# 086-005.net
KiCad netlist of a schematic drawn in EAGLE
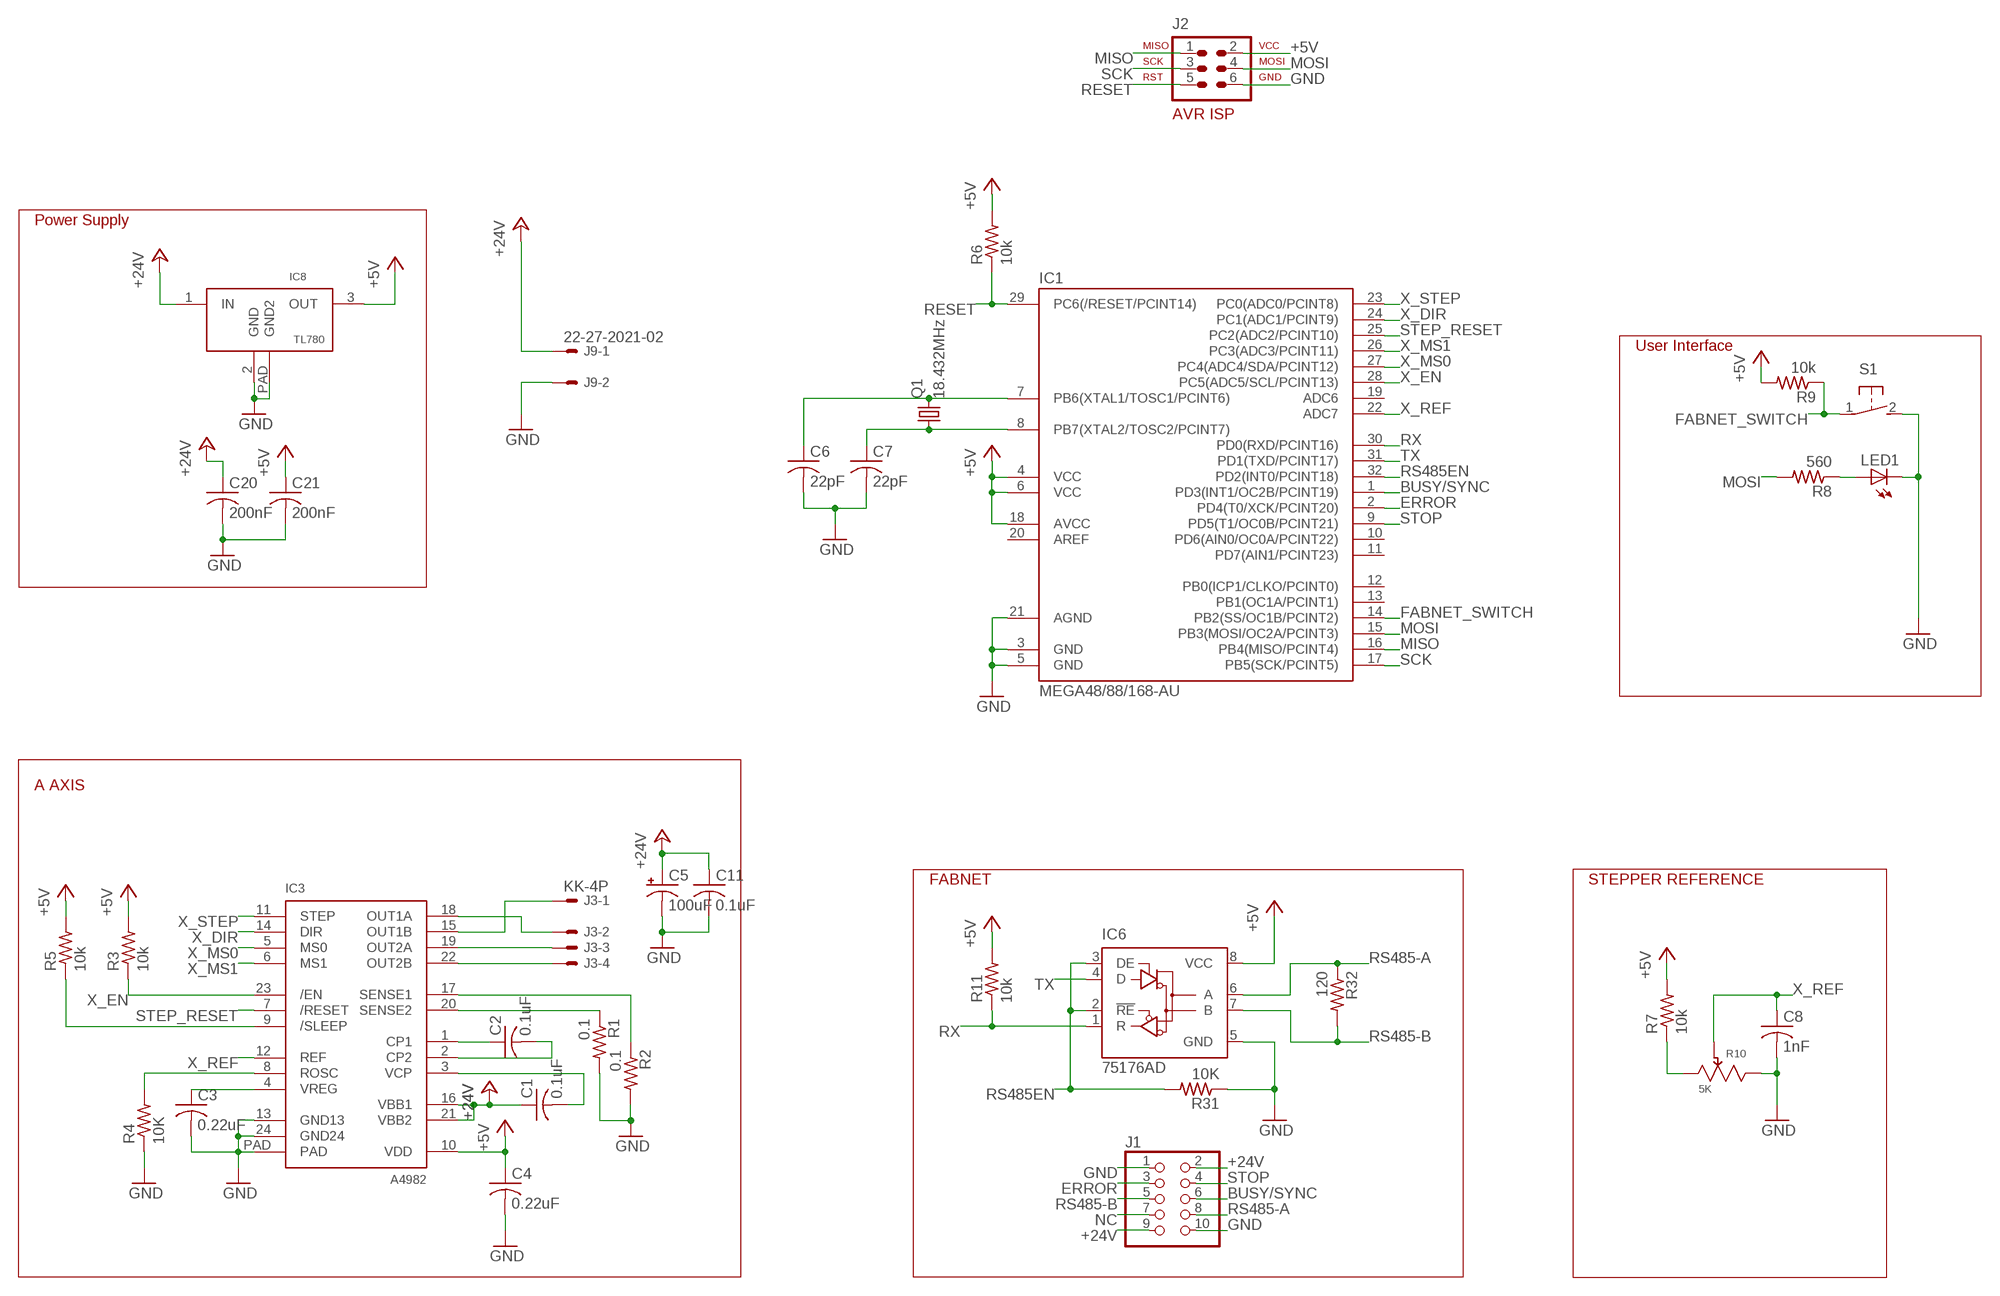
[diagram p0: schematic, sheet 1]

(export (version "E")
  (design (tool "Eeschema 10.0.6"))
  (components
    (comp (ref "C1")
      (value "0.1uF")
      (footprint "eagle-import:C0805")
      (libsource (lib "eagle-import") (part "C-USC0805"))
    )
    (comp (ref "C2")
      (value "0.1uF")
      (footprint "eagle-import:C0805")
      (libsource (lib "eagle-import") (part "C-USC0805"))
    )
    (comp (ref "C3")
      (value "0.22uF")
      (footprint "eagle-import:C0805")
      (libsource (lib "eagle-import") (part "C-USC0805"))
    )
    (comp (ref "C4")
      (value "0.22uF")
      (footprint "eagle-import:C0805")
      (libsource (lib "eagle-import") (part "C-USC0805"))
    )
    (comp (ref "C5")
      (value "100uF")
      (footprint "eagle-import:PANASONIC_D")
      (libsource (lib "eagle-import") (part "CPOL-USD"))
    )
    (comp (ref "C6")
      (value "22pF")
      (footprint "eagle-import:C0805")
      (libsource (lib "eagle-import") (part "C-USC0805"))
    )
    (comp (ref "C7")
      (value "22pF")
      (footprint "eagle-import:C0805")
      (libsource (lib "eagle-import") (part "C-USC0805"))
    )
    (comp (ref "C8")
      (value "1nF")
      (footprint "eagle-import:C0805")
      (libsource (lib "eagle-import") (part "C-USC0805"))
    )
    (comp (ref "C11")
      (value "0.1uF")
      (footprint "eagle-import:C0805")
      (libsource (lib "eagle-import") (part "C-USC0805"))
    )
    (comp (ref "C20")
      (value "200nF")
      (footprint "eagle-import:C0805")
      (libsource (lib "eagle-import") (part "C-USC0805"))
    )
    (comp (ref "C21")
      (value "200nF")
      (footprint "eagle-import:C0805")
      (libsource (lib "eagle-import") (part "C-USC0805"))
    )
    (comp (ref "IC1")
      (value "MEGA48/88/168-AU")
      (footprint "eagle-import:TQFP32-08")
      (libsource (lib "eagle-import") (part "MEGA48/88/168-AU"))
    )
    (comp (ref "IC3")
      (value "A4982")
      (footprint "eagle-import:TSSOP24_LP")
      (libsource (lib "eagle-import") (part "A4982"))
    )
    (comp (ref "IC6")
      (value "75176AD")
      (footprint "eagle-import:D_R-PDSO-G8")
      (libsource (lib "eagle-import") (part "75176AD"))
    )
    (comp (ref "IC8")
      (value "TL780_VREG")
      (footprint "eagle-import:D2PAK-3")
      (libsource (lib "eagle-import") (part "TL780_VREG"))
    )
    (comp (ref "J1")
      (value "PINHD-2X5")
      (footprint "eagle-import:2X05")
      (libsource (lib "eagle-import") (part "PINHD-2X5"))
    )
    (comp (ref "J2")
      (value "AVR-ISP-6VERT")
      (footprint "eagle-import:AVR-ISP-6")
      (libsource (lib "eagle-import") (part "AVR-ISP-6VERT"))
    )
    (comp (ref "J3")
      (value "KK-4P")
      (footprint "eagle-import:7395-04")
      (libsource (lib "eagle-import") (part "22-?-0405-7048"))
    )
    (comp (ref "J9")
      (value "22-27-2021-02")
      (footprint "eagle-import:6410-02")
      (libsource (lib "eagle-import") (part "22-?-0227-2021"))
    )
    (comp (ref "LED1")
      (value "LEDCHIPLED_0603")
      (footprint "eagle-import:CHIPLED_0603")
      (libsource (lib "eagle-import") (part "LEDCHIPLED_0603"))
    )
    (comp (ref "Q1")
      (value "18.432MHz")
      (footprint "eagle-import:HC49UP")
      (fields (field (name "OC_FARNELL") "unknown") (field (name "OC_NEWARK") "unknown"))
      (libsource (lib "eagle-import") (part "CRYSTALHC49UP"))
    )
    (comp (ref "R1")
      (value "0.1")
      (footprint "eagle-import:R1206")
      (libsource (lib "eagle-import") (part "R-US_R1206"))
    )
    (comp (ref "R2")
      (value "0.1")
      (footprint "eagle-import:R1206")
      (libsource (lib "eagle-import") (part "R-US_R1206"))
    )
    (comp (ref "R3")
      (value "10k")
      (footprint "eagle-import:R0805")
      (libsource (lib "eagle-import") (part "R-US_R0805"))
    )
    (comp (ref "R4")
      (value "10K")
      (footprint "eagle-import:R0805")
      (libsource (lib "eagle-import") (part "R-US_R0805"))
    )
    (comp (ref "R5")
      (value "10k")
      (footprint "eagle-import:R0805")
      (libsource (lib "eagle-import") (part "R-US_R0805"))
    )
    (comp (ref "R6")
      (value "10k")
      (footprint "eagle-import:R0805")
      (libsource (lib "eagle-import") (part "R-US_R0805"))
    )
    (comp (ref "R7")
      (value "10k")
      (footprint "eagle-import:R0805")
      (libsource (lib "eagle-import") (part "R-US_R0805"))
    )
    (comp (ref "R8")
      (value "560")
      (footprint "eagle-import:R0805")
      (libsource (lib "eagle-import") (part "R-US_R0805"))
    )
    (comp (ref "R9")
      (value "10k")
      (footprint "eagle-import:R0805")
      (libsource (lib "eagle-import") (part "R-US_R0805"))
    )
    (comp (ref "R10")
      (value "5K")
      (footprint "eagle-import:BOURN_TRIM")
      (libsource (lib "eagle-import") (part "BOURN_POT"))
    )
    (comp (ref "R11")
      (value "10k")
      (footprint "eagle-import:R0805")
      (libsource (lib "eagle-import") (part "R-US_R0805"))
    )
    (comp (ref "R31")
      (value "10K")
      (footprint "eagle-import:R0805")
      (libsource (lib "eagle-import") (part "R-US_R0805"))
    )
    (comp (ref "R32")
      (value "120")
      (footprint "eagle-import:R0805")
      (libsource (lib "eagle-import") (part "R-US_R0805"))
    )
    (comp (ref "S1")
      (value "31-XX")
      (footprint "eagle-import:B3F-31XX")
      (fields (field (name "MPN") "B3F-3100"))
      (libsource (lib "eagle-import") (part "31-XX"))
    )
  )
  (nets
    (net (code "1") (name "+5V") (class "Default")
      (node (ref "C21") (pin "1") (pinfunction "1_1") (pintype "passive"))
      (node (ref "C4") (pin "1") (pinfunction "1_1") (pintype "passive"))
      (node (ref "IC1") (pin "18") (pinfunction "AVCC_18") (pintype "passive"))
      (node (ref "IC1") (pin "4") (pinfunction "VCC_4") (pintype "power_in"))
      (node (ref "IC1") (pin "6") (pinfunction "VCC_6") (pintype "power_in"))
      (node (ref "IC3") (pin "10") (pinfunction "VDD_10") (pintype "bidirectional"))
      (node (ref "IC6") (pin "8") (pinfunction "VCC_8") (pintype "power_in"))
      (node (ref "IC8") (pin "3") (pinfunction "OUT_3") (pintype "bidirectional"))
      (node (ref "J2") (pin "2") (pinfunction "2_2") (pintype "passive"))
      (node (ref "R11") (pin "2") (pinfunction "2_2") (pintype "passive"))
      (node (ref "R3") (pin "2") (pinfunction "2_2") (pintype "passive"))
      (node (ref "R5") (pin "2") (pinfunction "2_2") (pintype "passive"))
      (node (ref "R6") (pin "2") (pinfunction "2_2") (pintype "passive"))
      (node (ref "R7") (pin "2") (pinfunction "2_2") (pintype "passive"))
      (node (ref "R9") (pin "2") (pinfunction "2_2") (pintype "passive"))
    )
    (net (code "2") (name "+24V") (class "Default")
      (node (ref "C1") (pin "1") (pinfunction "1_1") (pintype "passive"))
      (node (ref "C11") (pin "1") (pinfunction "1_1") (pintype "passive"))
      (node (ref "C20") (pin "1") (pinfunction "1_1") (pintype "passive"))
      (node (ref "C5") (pin "+") (pinfunction "+_+") (pintype "passive"))
      (node (ref "IC3") (pin "16") (pinfunction "VBB1_16") (pintype "bidirectional"))
      (node (ref "IC3") (pin "21") (pinfunction "VBB2_21") (pintype "bidirectional"))
      (node (ref "IC8") (pin "1") (pinfunction "IN_1") (pintype "bidirectional"))
      (node (ref "J1") (pin "2") (pinfunction "2_2") (pintype "passive"))
      (node (ref "J1") (pin "9") (pinfunction "9_9") (pintype "passive"))
      (node (ref "J9") (pin "1") (pinfunction "S_1") (pintype "passive"))
    )
    (net (code "3") (name "/BUSY{slash}SYNC") (class "Default")
      (node (ref "IC1") (pin "1") (pinfunction "PD3(INT1/OC2B/PCINT19)_1") (pintype "bidirectional"))
      (node (ref "J1") (pin "6") (pinfunction "6_6") (pintype "passive"))
    )
    (net (code "4") (name "/ERROR") (class "Default")
      (node (ref "IC1") (pin "2") (pinfunction "PD4(T0/XCK/PCINT20)_2") (pintype "bidirectional"))
      (node (ref "J1") (pin "3") (pinfunction "3_3") (pintype "passive"))
    )
    (net (code "5") (name "/FABNET_SWITCH") (class "Default")
      (node (ref "IC1") (pin "14") (pinfunction "PB2(SS/OC1B/PCINT2)_14") (pintype "bidirectional"))
      (node (ref "R9") (pin "1") (pinfunction "1_1") (pintype "passive"))
      (node (ref "S1") (pin "1") (pinfunction "P_1") (pintype "passive"))
    )
    (net (code "6") (name "/MISO") (class "Default")
      (node (ref "IC1") (pin "16") (pinfunction "PB4(MISO/PCINT4)_16") (pintype "bidirectional"))
      (node (ref "J2") (pin "1") (pinfunction "1_1") (pintype "passive"))
    )
    (net (code "7") (name "/MOSI") (class "Default")
      (node (ref "IC1") (pin "15") (pinfunction "PB3(MOSI/OC2A/PCINT3)_15") (pintype "bidirectional"))
      (node (ref "J2") (pin "4") (pinfunction "4_4") (pintype "passive"))
      (node (ref "R8") (pin "2") (pinfunction "2_2") (pintype "passive"))
    )
    (net (code "8") (name "/NC") (class "Default")
      (node (ref "J1") (pin "7") (pinfunction "7_7") (pintype "passive"))
    )
    (net (code "9") (name "/RESET") (class "Default")
      (node (ref "IC1") (pin "29") (pinfunction "PC6(/RESET/PCINT14)_29") (pintype "bidirectional"))
      (node (ref "J2") (pin "5") (pinfunction "5_5") (pintype "passive"))
      (node (ref "R6") (pin "1") (pinfunction "1_1") (pintype "passive"))
    )
    (net (code "10") (name "/RS485-A") (class "Default")
      (node (ref "IC6") (pin "6") (pinfunction "A_6") (pintype "output"))
      (node (ref "J1") (pin "8") (pinfunction "8_8") (pintype "passive"))
      (node (ref "R32") (pin "1") (pinfunction "1_1") (pintype "passive"))
    )
    (net (code "11") (name "/RS485-B") (class "Default")
      (node (ref "IC6") (pin "7") (pinfunction "B_7") (pintype "output"))
      (node (ref "J1") (pin "5") (pinfunction "5_5") (pintype "passive"))
      (node (ref "R32") (pin "2") (pinfunction "2_2") (pintype "passive"))
    )
    (net (code "12") (name "/RS485EN") (class "Default")
      (node (ref "IC1") (pin "32") (pinfunction "PD2(INT0/PCINT18)_32") (pintype "bidirectional"))
      (node (ref "IC6") (pin "2") (pinfunction "~{RE}_2") (pintype "input"))
      (node (ref "IC6") (pin "3") (pinfunction "DE_3") (pintype "input"))
      (node (ref "R31") (pin "2") (pinfunction "2_2") (pintype "passive"))
    )
    (net (code "13") (name "/RX") (class "Default")
      (node (ref "IC1") (pin "30") (pinfunction "PD0(RXD/PCINT16)_30") (pintype "bidirectional"))
      (node (ref "IC6") (pin "1") (pinfunction "R_1") (pintype "input"))
      (node (ref "R11") (pin "1") (pinfunction "1_1") (pintype "passive"))
    )
    (net (code "14") (name "/SCK") (class "Default")
      (node (ref "IC1") (pin "17") (pinfunction "PB5(SCK/PCINT5)_17") (pintype "bidirectional"))
      (node (ref "J2") (pin "3") (pinfunction "3_3") (pintype "passive"))
    )
    (net (code "15") (name "/STEP_RESET") (class "Default")
      (node (ref "IC1") (pin "25") (pinfunction "PC2(ADC2/PCINT10)_25") (pintype "bidirectional"))
      (node (ref "IC3") (pin "7") (pinfunction "/RESET_7") (pintype "bidirectional"))
    )
    (net (code "16") (name "/STOP") (class "Default")
      (node (ref "IC1") (pin "9") (pinfunction "PD5(T1/OC0B/PCINT21)_9") (pintype "bidirectional"))
      (node (ref "J1") (pin "4") (pinfunction "4_4") (pintype "passive"))
    )
    (net (code "17") (name "/TX") (class "Default")
      (node (ref "IC1") (pin "31") (pinfunction "PD1(TXD/PCINT17)_31") (pintype "bidirectional"))
      (node (ref "IC6") (pin "4") (pinfunction "D_4") (pintype "input"))
    )
    (net (code "18") (name "/X_DIR") (class "Default")
      (node (ref "IC1") (pin "24") (pinfunction "PC1(ADC1/PCINT9)_24") (pintype "bidirectional"))
      (node (ref "IC3") (pin "14") (pinfunction "DIR_14") (pintype "bidirectional"))
    )
    (net (code "19") (name "/X_EN") (class "Default")
      (node (ref "IC1") (pin "28") (pinfunction "PC5(ADC5/SCL/PCINT13)_28") (pintype "bidirectional"))
      (node (ref "IC3") (pin "23") (pinfunction "/EN_23") (pintype "bidirectional"))
      (node (ref "R3") (pin "1") (pinfunction "1_1") (pintype "passive"))
    )
    (net (code "20") (name "/X_MS0") (class "Default")
      (node (ref "IC1") (pin "27") (pinfunction "PC4(ADC4/SDA/PCINT12)_27") (pintype "bidirectional"))
      (node (ref "IC3") (pin "5") (pinfunction "MS0_5") (pintype "bidirectional"))
    )
    (net (code "21") (name "/X_MS1") (class "Default")
      (node (ref "IC1") (pin "26") (pinfunction "PC3(ADC3/PCINT11)_26") (pintype "bidirectional"))
      (node (ref "IC3") (pin "6") (pinfunction "MS1_6") (pintype "bidirectional"))
    )
    (net (code "22") (name "/X_REF") (class "Default")
      (node (ref "C8") (pin "1") (pinfunction "1_1") (pintype "passive"))
      (node (ref "IC1") (pin "22") (pinfunction "ADC7_22") (pintype "passive"))
      (node (ref "IC3") (pin "12") (pinfunction "REF_12") (pintype "bidirectional"))
      (node (ref "R10") (pin "2") (pinfunction "2_2") (pintype "bidirectional"))
    )
    (net (code "23") (name "/X_STEP") (class "Default")
      (node (ref "IC1") (pin "23") (pinfunction "PC0(ADC0/PCINT8)_23") (pintype "bidirectional"))
      (node (ref "IC3") (pin "11") (pinfunction "STEP_11") (pintype "bidirectional"))
    )
    (net (code "24") (name "GND") (class "Default")
      (node (ref "C11") (pin "2") (pinfunction "2_2") (pintype "passive"))
      (node (ref "C20") (pin "2") (pinfunction "2_2") (pintype "passive"))
      (node (ref "C21") (pin "2") (pinfunction "2_2") (pintype "passive"))
      (node (ref "C3") (pin "2") (pinfunction "2_2") (pintype "passive"))
      (node (ref "C4") (pin "2") (pinfunction "2_2") (pintype "passive"))
      (node (ref "C5") (pin "-") (pinfunction "-_-") (pintype "passive"))
      (node (ref "C6") (pin "2") (pinfunction "2_2") (pintype "passive"))
      (node (ref "C7") (pin "2") (pinfunction "2_2") (pintype "passive"))
      (node (ref "C8") (pin "2") (pinfunction "2_2") (pintype "passive"))
      (node (ref "IC1") (pin "21") (pinfunction "AGND_21") (pintype "power_in"))
      (node (ref "IC1") (pin "3") (pinfunction "GND_3") (pintype "power_in"))
      (node (ref "IC1") (pin "5") (pinfunction "GND_5") (pintype "power_in"))
      (node (ref "IC3") (pin "13") (pinfunction "GND13_13") (pintype "bidirectional"))
      (node (ref "IC3") (pin "24") (pinfunction "GND24_24") (pintype "bidirectional"))
      (node (ref "IC3") (pin "PAD") (pinfunction "PAD_PAD") (pintype "bidirectional"))
      (node (ref "IC6") (pin "5") (pinfunction "GND_5") (pintype "power_in"))
      (node (ref "IC8") (pin "2") (pinfunction "GND_2") (pintype "bidirectional"))
      (node (ref "IC8") (pin "PAD") (pinfunction "GND2_PAD") (pintype "bidirectional"))
      (node (ref "J1") (pin "1") (pinfunction "1_1") (pintype "passive"))
      (node (ref "J1") (pin "10") (pinfunction "10_10") (pintype "passive"))
      (node (ref "J2") (pin "6") (pinfunction "6_6") (pintype "passive"))
      (node (ref "J9") (pin "2") (pinfunction "S_2") (pintype "passive"))
      (node (ref "LED1") (pin "C") (pinfunction "C_C") (pintype "passive"))
      (node (ref "R1") (pin "2") (pinfunction "2_2") (pintype "passive"))
      (node (ref "R10") (pin "3") (pinfunction "3_3") (pintype "bidirectional"))
      (node (ref "R2") (pin "2") (pinfunction "2_2") (pintype "passive"))
      (node (ref "R31") (pin "1") (pinfunction "1_1") (pintype "passive"))
      (node (ref "R4") (pin "1") (pinfunction "1_1") (pintype "passive"))
      (node (ref "S1") (pin "2") (pinfunction "S_2") (pintype "passive"))
    )
    (net (code "25") (name "Net-(IC1-PB6(XTAL1{slash}TOSC1{slash}PCINT6))") (class "Default")
      (node (ref "C6") (pin "1") (pinfunction "1_1") (pintype "passive"))
      (node (ref "IC1") (pin "7") (pinfunction "PB6(XTAL1/TOSC1/PCINT6)_7") (pintype "bidirectional"))
      (node (ref "Q1") (pin "2") (pinfunction "2_2") (pintype "passive"))
    )
    (net (code "26") (name "Net-(IC1-PB7(XTAL2{slash}TOSC2{slash}PCINT7))") (class "Default")
      (node (ref "C7") (pin "1") (pinfunction "1_1") (pintype "passive"))
      (node (ref "IC1") (pin "8") (pinfunction "PB7(XTAL2/TOSC2/PCINT7)_8") (pintype "bidirectional"))
      (node (ref "Q1") (pin "1") (pinfunction "1_1") (pintype "passive"))
    )
    (net (code "27") (name "Net-(IC3-CP1)") (class "Default")
      (node (ref "C2") (pin "1") (pinfunction "1_1") (pintype "passive"))
      (node (ref "IC3") (pin "1") (pinfunction "CP1_1") (pintype "bidirectional"))
    )
    (net (code "28") (name "Net-(IC3-CP2)") (class "Default")
      (node (ref "C2") (pin "2") (pinfunction "2_2") (pintype "passive"))
      (node (ref "IC3") (pin "2") (pinfunction "CP2_2") (pintype "bidirectional"))
    )
    (net (code "29") (name "Net-(IC3-OUT1A)") (class "Default")
      (node (ref "IC3") (pin "18") (pinfunction "OUT1A_18") (pintype "bidirectional"))
      (node (ref "J3") (pin "2") (pinfunction "S_2") (pintype "passive"))
    )
    (net (code "30") (name "Net-(IC3-OUT1B)") (class "Default")
      (node (ref "IC3") (pin "15") (pinfunction "OUT1B_15") (pintype "bidirectional"))
      (node (ref "J3") (pin "1") (pinfunction "S_1") (pintype "passive"))
    )
    (net (code "31") (name "Net-(IC3-OUT2A)") (class "Default")
      (node (ref "IC3") (pin "19") (pinfunction "OUT2A_19") (pintype "bidirectional"))
      (node (ref "J3") (pin "3") (pinfunction "S_3") (pintype "passive"))
    )
    (net (code "32") (name "Net-(IC3-OUT2B)") (class "Default")
      (node (ref "IC3") (pin "22") (pinfunction "OUT2B_22") (pintype "bidirectional"))
      (node (ref "J3") (pin "4") (pinfunction "S_4") (pintype "passive"))
    )
    (net (code "33") (name "Net-(IC3-ROSC)") (class "Default")
      (node (ref "IC3") (pin "8") (pinfunction "ROSC_8") (pintype "bidirectional"))
      (node (ref "R4") (pin "2") (pinfunction "2_2") (pintype "passive"))
    )
    (net (code "34") (name "Net-(IC3-SENSE1)") (class "Default")
      (node (ref "IC3") (pin "17") (pinfunction "SENSE1_17") (pintype "bidirectional"))
      (node (ref "R2") (pin "1") (pinfunction "1_1") (pintype "passive"))
    )
    (net (code "35") (name "Net-(IC3-SENSE2)") (class "Default")
      (node (ref "IC3") (pin "20") (pinfunction "SENSE2_20") (pintype "bidirectional"))
      (node (ref "R1") (pin "1") (pinfunction "1_1") (pintype "passive"))
    )
    (net (code "36") (name "Net-(IC3-VCP)") (class "Default")
      (node (ref "C1") (pin "2") (pinfunction "2_2") (pintype "passive"))
      (node (ref "IC3") (pin "3") (pinfunction "VCP_3") (pintype "bidirectional"))
    )
    (net (code "37") (name "Net-(IC3-VREG)") (class "Default")
      (node (ref "C3") (pin "1") (pinfunction "1_1") (pintype "passive"))
      (node (ref "IC3") (pin "4") (pinfunction "VREG_4") (pintype "bidirectional"))
    )
    (net (code "38") (name "Net-(IC3-{slash}SLEEP)") (class "Default")
      (node (ref "IC3") (pin "9") (pinfunction "/SLEEP_9") (pintype "bidirectional"))
      (node (ref "R5") (pin "1") (pinfunction "1_1") (pintype "passive"))
    )
    (net (code "39") (name "Net-(LED1-PadA)") (class "Default")
      (node (ref "LED1") (pin "A") (pinfunction "A_A") (pintype "passive"))
      (node (ref "R8") (pin "1") (pinfunction "1_1") (pintype "passive"))
    )
    (net (code "40") (name "Net-(R10-Pad1)") (class "Default")
      (node (ref "R10") (pin "1") (pinfunction "1_1") (pintype "bidirectional"))
      (node (ref "R7") (pin "1") (pinfunction "1_1") (pintype "passive"))
    )
    (net (code "41") (name "unconnected-(IC1-ADC6-Pad19)") (class "Default")
      (node (ref "IC1") (pin "19") (pinfunction "ADC6_19") (pintype "passive"))
    )
    (net (code "42") (name "unconnected-(IC1-AREF-Pad20)") (class "Default")
      (node (ref "IC1") (pin "20") (pinfunction "AREF_20") (pintype "passive"))
    )
    (net (code "43") (name "unconnected-(IC1-PB0(ICP1{slash}CLKO{slash}PCINT0)-Pad12)") (class "Default")
      (node (ref "IC1") (pin "12") (pinfunction "PB0(ICP1/CLKO/PCINT0)_12") (pintype "bidirectional"))
    )
    (net (code "44") (name "unconnected-(IC1-PB1(OC1A{slash}PCINT1)-Pad13)") (class "Default")
      (node (ref "IC1") (pin "13") (pinfunction "PB1(OC1A/PCINT1)_13") (pintype "bidirectional"))
    )
    (net (code "45") (name "unconnected-(IC1-PD6(AIN0{slash}OC0A{slash}PCINT22)-Pad10)") (class "Default")
      (node (ref "IC1") (pin "10") (pinfunction "PD6(AIN0/OC0A/PCINT22)_10") (pintype "bidirectional"))
    )
    (net (code "46") (name "unconnected-(IC1-PD7(AIN1{slash}PCINT23)-Pad11)") (class "Default")
      (node (ref "IC1") (pin "11") (pinfunction "PD7(AIN1/PCINT23)_11") (pintype "bidirectional"))
    )
  )
)
